# EZS.net
KiCad netlist of a schematic drawn in EAGLE
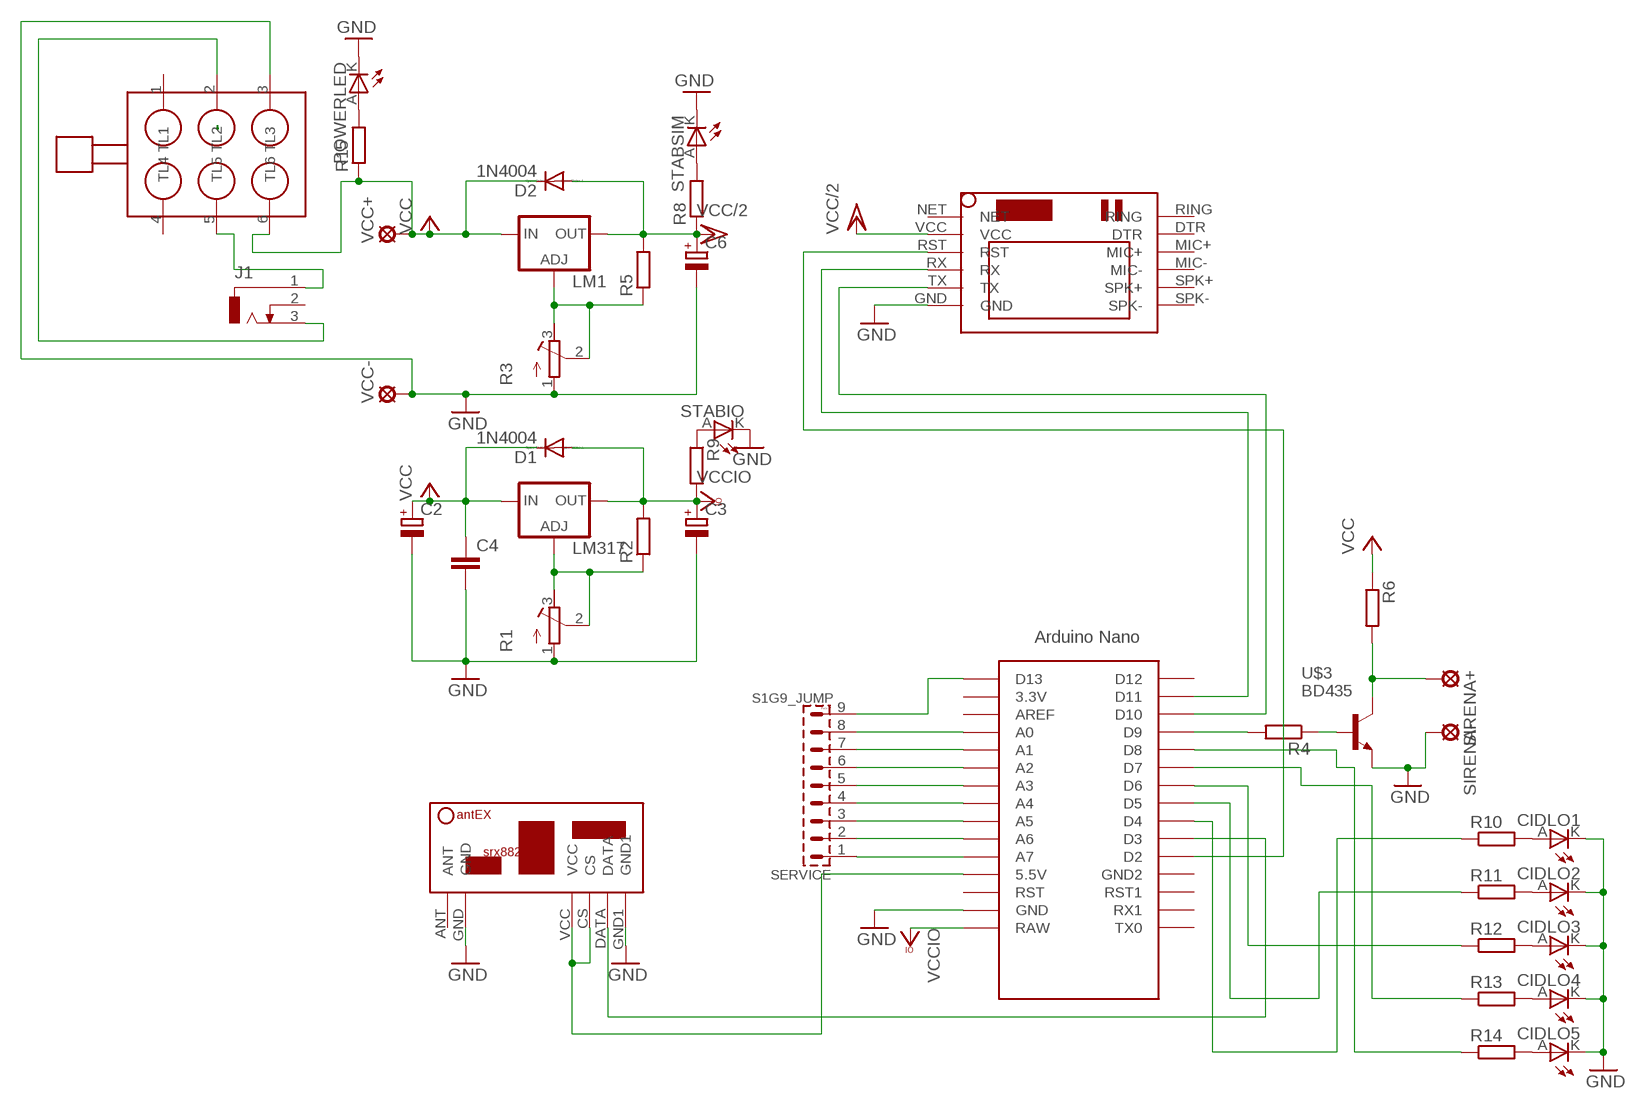
[diagram p0: schematic, sheet 1]

(export (version "E")
  (design (tool "Eeschema 10.0.6"))
  (components
    (comp (ref "C2")
      (value "CPOL-EUE3.5-8")
      (footprint "eagle-import:E3,5-8")
      (libsource (lib "eagle-import") (part "CPOL-EUE3.5-8"))
    )
    (comp (ref "C3")
      (value "CPOL-EUE3.5-8")
      (footprint "eagle-import:E3,5-8")
      (libsource (lib "eagle-import") (part "CPOL-EUE3.5-8"))
    )
    (comp (ref "C4")
      (value "C-EU102-064X133")
      (footprint "eagle-import:C102-064X133")
      (libsource (lib "eagle-import") (part "C-EU102-064X133"))
    )
    (comp (ref "C6")
      (value "CPOL-EUE3.5-8")
      (footprint "eagle-import:E3,5-8")
      (libsource (lib "eagle-import") (part "CPOL-EUE3.5-8"))
    )
    (comp (ref "CIDLO1")
      (value "LEDLED3MM")
      (footprint "eagle-import:LED3MM")
      (libsource (lib "eagle-import") (part "LEDLED3MM"))
    )
    (comp (ref "CIDLO2")
      (value "LEDLED3MM")
      (footprint "eagle-import:LED3MM")
      (libsource (lib "eagle-import") (part "LEDLED3MM"))
    )
    (comp (ref "CIDLO3")
      (value "LEDLED3MM")
      (footprint "eagle-import:LED3MM")
      (libsource (lib "eagle-import") (part "LEDLED3MM"))
    )
    (comp (ref "CIDLO4")
      (value "LEDLED3MM")
      (footprint "eagle-import:LED3MM")
      (libsource (lib "eagle-import") (part "LEDLED3MM"))
    )
    (comp (ref "CIDLO5")
      (value "LEDLED3MM")
      (footprint "eagle-import:LED3MM")
      (libsource (lib "eagle-import") (part "LEDLED3MM"))
    )
    (comp (ref "D1")
      (value "1N4004")
      (footprint "eagle-import:DO41-10")
      (libsource (lib "eagle-import") (part "1N4004"))
    )
    (comp (ref "D2")
      (value "1N4004")
      (footprint "eagle-import:DO41-10")
      (libsource (lib "eagle-import") (part "1N4004"))
    )
    (comp (ref "J1")
      (value "DCJ0303")
      (footprint "eagle-import:DCJ0303")
      (libsource (lib "eagle-import") (part "DCJ0303"))
    )
    (comp (ref "LM1")
      (value "LM317TS")
      (footprint "eagle-import:317TS")
      (libsource (lib "eagle-import") (part "LM317TS"))
    )
    (comp (ref "LM317")
      (value "LM317TS")
      (footprint "eagle-import:317TS")
      (libsource (lib "eagle-import") (part "LM317TS"))
    )
    (comp (ref "POWERLED")
      (value "LEDLED3MM")
      (footprint "eagle-import:LED3MM")
      (libsource (lib "eagle-import") (part "LEDLED3MM"))
    )
    (comp (ref "R1")
      (value "R-TRIMM64Y")
      (footprint "eagle-import:RTRIM64Y")
      (libsource (lib "eagle-import") (part "R-TRIMM64Y"))
    )
    (comp (ref "R2")
      (value "R-EU_0207/10")
      (footprint "eagle-import:0207_10")
      (libsource (lib "eagle-import") (part "R-EU_0207/10"))
    )
    (comp (ref "R3")
      (value "R-TRIMM64Y")
      (footprint "eagle-import:RTRIM64Y")
      (libsource (lib "eagle-import") (part "R-TRIMM64Y"))
    )
    (comp (ref "R4")
      (value "R-EU_0207/10")
      (footprint "eagle-import:0207_10")
      (libsource (lib "eagle-import") (part "R-EU_0207/10"))
    )
    (comp (ref "R5")
      (value "R-EU_0207/10")
      (footprint "eagle-import:0207_10")
      (libsource (lib "eagle-import") (part "R-EU_0207/10"))
    )
    (comp (ref "R6")
      (value "R-EU_0207/10")
      (footprint "eagle-import:0207_10")
      (libsource (lib "eagle-import") (part "R-EU_0207/10"))
    )
    (comp (ref "R8")
      (value "R-EU_0207/10")
      (footprint "eagle-import:0207_10")
      (libsource (lib "eagle-import") (part "R-EU_0207/10"))
    )
    (comp (ref "R9")
      (value "R-EU_0207/10")
      (footprint "eagle-import:0207_10")
      (libsource (lib "eagle-import") (part "R-EU_0207/10"))
    )
    (comp (ref "R10")
      (value "R-EU_0207/10")
      (footprint "eagle-import:0207_10")
      (libsource (lib "eagle-import") (part "R-EU_0207/10"))
    )
    (comp (ref "R11")
      (value "R-EU_0207/10")
      (footprint "eagle-import:0207_10")
      (libsource (lib "eagle-import") (part "R-EU_0207/10"))
    )
    (comp (ref "R12")
      (value "R-EU_0207/10")
      (footprint "eagle-import:0207_10")
      (libsource (lib "eagle-import") (part "R-EU_0207/10"))
    )
    (comp (ref "R13")
      (value "R-EU_0207/10")
      (footprint "eagle-import:0207_10")
      (libsource (lib "eagle-import") (part "R-EU_0207/10"))
    )
    (comp (ref "R14")
      (value "R-EU_0207/10")
      (footprint "eagle-import:0207_10")
      (libsource (lib "eagle-import") (part "R-EU_0207/10"))
    )
    (comp (ref "R15")
      (value "R-EU_0207/10")
      (footprint "eagle-import:0207_10")
      (libsource (lib "eagle-import") (part "R-EU_0207/10"))
    )
    (comp (ref "SERVICE")
      (value "S1G9_JUMP")
      (footprint "eagle-import:S1G9_JUM")
      (libsource (lib "eagle-import") (part "S1G9_JUMP"))
    )
    (comp (ref "SIM800L")
      (value "SIM800LMODULE")
      (footprint "eagle-import:SIM800LMODULE")
      (libsource (lib "eagle-import") (part "SIM800LMODULE"))
    )
    (comp (ref "SIRENA+")
      (value "LSP11")
      (footprint "eagle-import:LSP11")
      (libsource (lib "eagle-import") (part "LSP11"))
    )
    (comp (ref "SIRENA-")
      (value "LSP11")
      (footprint "eagle-import:LSP11")
      (libsource (lib "eagle-import") (part "LSP11"))
    )
    (comp (ref "STABIO")
      (value "LEDLED3MM")
      (footprint "eagle-import:LED3MM")
      (libsource (lib "eagle-import") (part "LEDLED3MM"))
    )
    (comp (ref "STABSIM")
      (value "LEDLED3MM")
      (footprint "eagle-import:LED3MM")
      (libsource (lib "eagle-import") (part "LEDLED3MM"))
    )
    (comp (ref "U$1")
      (value "NANO")
      (footprint "eagle-import:NANO")
      (libsource (lib "eagle-import") (part "NANO"))
    )
    (comp (ref "U$2")
      (value "RSX882")
      (footprint "eagle-import:SRX882")
      (libsource (lib "eagle-import") (part "RSX882"))
    )
    (comp (ref "U$3")
      (value "BD435")
      (footprint "eagle-import:BD435")
      (libsource (lib "eagle-import") (part "BD435"))
    )
    (comp (ref "U$4")
      (value "TLACITKO")
      (footprint "eagle-import:TLACITKO")
      (libsource (lib "eagle-import") (part "TLACITKO"))
    )
    (comp (ref "VCC+")
      (value "LSP11")
      (footprint "eagle-import:LSP11")
      (libsource (lib "eagle-import") (part "LSP11"))
    )
    (comp (ref "VCC-")
      (value "LSP11")
      (footprint "eagle-import:LSP11")
      (libsource (lib "eagle-import") (part "LSP11"))
    )
  )
  (nets
    (net (code "1") (name "GND") (class "Default")
      (node (ref "C2") (pin "-") (pinfunction "-_-") (pintype "passive"))
      (node (ref "C3") (pin "-") (pinfunction "-_-") (pintype "passive"))
      (node (ref "C4") (pin "2") (pinfunction "2_2") (pintype "passive"))
      (node (ref "C6") (pin "-") (pinfunction "-_-") (pintype "passive"))
      (node (ref "CIDLO1") (pin "K") (pinfunction "C_K") (pintype "passive"))
      (node (ref "CIDLO2") (pin "K") (pinfunction "C_K") (pintype "passive"))
      (node (ref "CIDLO3") (pin "K") (pinfunction "C_K") (pintype "passive"))
      (node (ref "CIDLO4") (pin "K") (pinfunction "C_K") (pintype "passive"))
      (node (ref "CIDLO5") (pin "K") (pinfunction "C_K") (pintype "passive"))
      (node (ref "POWERLED") (pin "K") (pinfunction "C_K") (pintype "passive"))
      (node (ref "R1") (pin "1") (pinfunction "A_1") (pintype "passive"))
      (node (ref "R3") (pin "1") (pinfunction "A_1") (pintype "passive"))
      (node (ref "SIM800L") (pin "GND") (pinfunction "GND_GND") (pintype "bidirectional"))
      (node (ref "SIRENA-") (pin "MP") (pinfunction "MP_MP") (pintype "passive"))
      (node (ref "STABIO") (pin "K") (pinfunction "C_K") (pintype "passive"))
      (node (ref "STABSIM") (pin "K") (pinfunction "C_K") (pintype "passive"))
      (node (ref "U$1") (pin "GND") (pinfunction "GND_GND") (pintype "bidirectional"))
      (node (ref "U$2") (pin "GND") (pinfunction "GND_GND") (pintype "bidirectional"))
      (node (ref "U$2") (pin "GND1") (pinfunction "GND1_GND1") (pintype "bidirectional"))
      (node (ref "U$3") (pin "E") (pinfunction "E_E") (pintype "passive"))
      (node (ref "U$4") (pin "3") (pinfunction "TL3_3") (pintype "bidirectional"))
      (node (ref "VCC-") (pin "MP") (pinfunction "MP_MP") (pintype "passive"))
    )
    (net (code "2") (name "Net-(CIDLO1-PadA)") (class "Default")
      (node (ref "CIDLO1") (pin "A") (pinfunction "A_A") (pintype "passive"))
      (node (ref "R10") (pin "2") (pinfunction "2_2") (pintype "passive"))
    )
    (net (code "3") (name "Net-(CIDLO2-PadA)") (class "Default")
      (node (ref "CIDLO2") (pin "A") (pinfunction "A_A") (pintype "passive"))
      (node (ref "R11") (pin "2") (pinfunction "2_2") (pintype "passive"))
    )
    (net (code "4") (name "Net-(CIDLO3-PadA)") (class "Default")
      (node (ref "CIDLO3") (pin "A") (pinfunction "A_A") (pintype "passive"))
      (node (ref "R12") (pin "2") (pinfunction "2_2") (pintype "passive"))
    )
    (net (code "5") (name "Net-(CIDLO4-PadA)") (class "Default")
      (node (ref "CIDLO4") (pin "A") (pinfunction "A_A") (pintype "passive"))
      (node (ref "R13") (pin "2") (pinfunction "2_2") (pintype "passive"))
    )
    (net (code "6") (name "Net-(CIDLO5-PadA)") (class "Default")
      (node (ref "CIDLO5") (pin "A") (pinfunction "A_A") (pintype "passive"))
      (node (ref "R14") (pin "2") (pinfunction "2_2") (pintype "passive"))
    )
    (net (code "7") (name "Net-(LM1-ADJ)") (class "Default")
      (node (ref "LM1") (pin "1") (pinfunction "ADJ_1") (pintype "input"))
      (node (ref "R3") (pin "2") (pinfunction "S_2") (pintype "passive"))
      (node (ref "R3") (pin "3") (pinfunction "E_3") (pintype "passive"))
      (node (ref "R5") (pin "1") (pinfunction "1_1") (pintype "passive"))
    )
    (net (code "8") (name "Net-(LM317-ADJ)") (class "Default")
      (node (ref "LM317") (pin "1") (pinfunction "ADJ_1") (pintype "input"))
      (node (ref "R1") (pin "2") (pinfunction "S_2") (pintype "passive"))
      (node (ref "R1") (pin "3") (pinfunction "E_3") (pintype "passive"))
      (node (ref "R2") (pin "1") (pinfunction "1_1") (pintype "passive"))
    )
    (net (code "9") (name "Net-(POWERLED-PadA)") (class "Default")
      (node (ref "POWERLED") (pin "A") (pinfunction "A_A") (pintype "passive"))
      (node (ref "R15") (pin "2") (pinfunction "2_2") (pintype "passive"))
    )
    (net (code "10") (name "Net-(R4-Pad1)") (class "Default")
      (node (ref "R4") (pin "1") (pinfunction "1_1") (pintype "passive"))
      (node (ref "U$3") (pin "B") (pinfunction "B_B") (pintype "passive"))
    )
    (net (code "11") (name "Net-(R4-Pad2)") (class "Default")
      (node (ref "R4") (pin "2") (pinfunction "2_2") (pintype "passive"))
      (node (ref "U$1") (pin "D9") (pinfunction "D9_D9") (pintype "bidirectional"))
    )
    (net (code "12") (name "Net-(R6-Pad2)") (class "Default")
      (node (ref "R6") (pin "2") (pinfunction "2_2") (pintype "passive"))
      (node (ref "SIRENA+") (pin "MP") (pinfunction "MP_MP") (pintype "passive"))
      (node (ref "U$3") (pin "C") (pinfunction "C_C") (pintype "passive"))
    )
    (net (code "13") (name "Net-(R8-Pad2)") (class "Default")
      (node (ref "R8") (pin "2") (pinfunction "2_2") (pintype "passive"))
      (node (ref "STABSIM") (pin "A") (pinfunction "A_A") (pintype "passive"))
    )
    (net (code "14") (name "Net-(R9-Pad1)") (class "Default")
      (node (ref "R9") (pin "1") (pinfunction "1_1") (pintype "passive"))
      (node (ref "STABIO") (pin "A") (pinfunction "A_A") (pintype "passive"))
    )
    (net (code "15") (name "Net-(R10-Pad1)") (class "Default")
      (node (ref "R10") (pin "1") (pinfunction "1_1") (pintype "passive"))
      (node (ref "U$1") (pin "D4") (pinfunction "D4_D4") (pintype "bidirectional"))
    )
    (net (code "16") (name "Net-(R11-Pad1)") (class "Default")
      (node (ref "R11") (pin "1") (pinfunction "1_1") (pintype "passive"))
      (node (ref "U$1") (pin "D5") (pinfunction "D5_D5") (pintype "bidirectional"))
    )
    (net (code "17") (name "Net-(R12-Pad1)") (class "Default")
      (node (ref "R12") (pin "1") (pinfunction "1_1") (pintype "passive"))
      (node (ref "U$1") (pin "D6") (pinfunction "D6_D6") (pintype "bidirectional"))
    )
    (net (code "18") (name "Net-(R13-Pad1)") (class "Default")
      (node (ref "R13") (pin "1") (pinfunction "1_1") (pintype "passive"))
      (node (ref "U$1") (pin "D7") (pinfunction "D7_D7") (pintype "bidirectional"))
    )
    (net (code "19") (name "Net-(R14-Pad1)") (class "Default")
      (node (ref "R14") (pin "1") (pinfunction "1_1") (pintype "passive"))
      (node (ref "U$1") (pin "D8") (pinfunction "D8_D8") (pintype "bidirectional"))
    )
    (net (code "20") (name "Net-(SERVICE-Pad1)") (class "Default")
      (node (ref "SERVICE") (pin "1") (pinfunction "1_1") (pintype "passive"))
      (node (ref "U$1") (pin "A7") (pinfunction "A7_A7") (pintype "bidirectional"))
    )
    (net (code "21") (name "Net-(SERVICE-Pad2)") (class "Default")
      (node (ref "SERVICE") (pin "2") (pinfunction "2_2") (pintype "passive"))
      (node (ref "U$1") (pin "A6") (pinfunction "A6_A6") (pintype "bidirectional"))
    )
    (net (code "22") (name "Net-(SERVICE-Pad3)") (class "Default")
      (node (ref "SERVICE") (pin "3") (pinfunction "3_3") (pintype "passive"))
      (node (ref "U$1") (pin "A5") (pinfunction "A5_A5") (pintype "bidirectional"))
    )
    (net (code "23") (name "Net-(SERVICE-Pad4)") (class "Default")
      (node (ref "SERVICE") (pin "4") (pinfunction "4_4") (pintype "passive"))
      (node (ref "U$1") (pin "A4") (pinfunction "A4_A4") (pintype "bidirectional"))
    )
    (net (code "24") (name "Net-(SERVICE-Pad5)") (class "Default")
      (node (ref "SERVICE") (pin "5") (pinfunction "5_5") (pintype "passive"))
      (node (ref "U$1") (pin "A3") (pinfunction "A3_A3") (pintype "bidirectional"))
    )
    (net (code "25") (name "Net-(SERVICE-Pad6)") (class "Default")
      (node (ref "SERVICE") (pin "6") (pinfunction "6_6") (pintype "passive"))
      (node (ref "U$1") (pin "A2") (pinfunction "A2_A2") (pintype "bidirectional"))
    )
    (net (code "26") (name "Net-(SERVICE-Pad7)") (class "Default")
      (node (ref "SERVICE") (pin "7") (pinfunction "7_7") (pintype "passive"))
      (node (ref "U$1") (pin "A1") (pinfunction "A1_A1") (pintype "bidirectional"))
    )
    (net (code "27") (name "Net-(SERVICE-Pad8)") (class "Default")
      (node (ref "SERVICE") (pin "8") (pinfunction "8_8") (pintype "passive"))
      (node (ref "U$1") (pin "A0") (pinfunction "A0_A0") (pintype "bidirectional"))
    )
    (net (code "28") (name "Net-(SERVICE-Pad9)") (class "Default")
      (node (ref "SERVICE") (pin "9") (pinfunction "9_9") (pintype "passive"))
      (node (ref "U$1") (pin "D13") (pinfunction "D13_D13") (pintype "bidirectional"))
    )
    (net (code "29") (name "Net-(SIM800L-PadRST)") (class "Default")
      (node (ref "SIM800L") (pin "RST") (pinfunction "RST_RST") (pintype "bidirectional"))
      (node (ref "U$1") (pin "D2") (pinfunction "D2_D2") (pintype "bidirectional"))
    )
    (net (code "30") (name "Net-(SIM800L-PadRX)") (class "Default")
      (node (ref "SIM800L") (pin "RX") (pinfunction "RX_RX") (pintype "bidirectional"))
      (node (ref "U$1") (pin "D11") (pinfunction "D11_D11") (pintype "bidirectional"))
    )
    (net (code "31") (name "Net-(SIM800L-PadTX)") (class "Default")
      (node (ref "SIM800L") (pin "TX") (pinfunction "TX_TX") (pintype "bidirectional"))
      (node (ref "U$1") (pin "D10") (pinfunction "D10_D10") (pintype "bidirectional"))
    )
    (net (code "32") (name "Net-(U$1-5.5V)") (class "Default")
      (node (ref "U$1") (pin "5V") (pinfunction "5.5V_5V") (pintype "bidirectional"))
      (node (ref "U$2") (pin "CS") (pinfunction "CS_CS") (pintype "bidirectional"))
      (node (ref "U$2") (pin "VCC") (pinfunction "VCC_VCC") (pintype "bidirectional"))
    )
    (net (code "33") (name "Net-(U$1-PadD3)") (class "Default")
      (node (ref "U$1") (pin "D3") (pinfunction "D3_D3") (pintype "bidirectional"))
      (node (ref "U$2") (pin "DATA") (pinfunction "DATA_DATA") (pintype "bidirectional"))
    )
    (net (code "34") (name "Net-(U$4-TL2)") (class "Default")
      (node (ref "J1") (pin "3") (pinfunction "3_3") (pintype "passive"))
      (node (ref "U$4") (pin "2") (pinfunction "TL2_2") (pintype "bidirectional"))
    )
    (net (code "35") (name "Net-(U$4-TL5)") (class "Default")
      (node (ref "J1") (pin "1") (pinfunction "1_1") (pintype "passive"))
      (node (ref "U$4") (pin "5") (pinfunction "TL5_5") (pintype "bidirectional"))
    )
    (net (code "36") (name "VCC") (class "Default")
      (node (ref "C2") (pin "+") (pinfunction "+_+") (pintype "passive"))
      (node (ref "C4") (pin "1") (pinfunction "1_1") (pintype "passive"))
      (node (ref "D1") (pin "C") (pinfunction "C_C") (pintype "passive"))
      (node (ref "D2") (pin "C") (pinfunction "C_C") (pintype "passive"))
      (node (ref "LM1") (pin "3") (pinfunction "IN_3") (pintype "input"))
      (node (ref "LM317") (pin "3") (pinfunction "IN_3") (pintype "input"))
      (node (ref "R15") (pin "1") (pinfunction "1_1") (pintype "passive"))
      (node (ref "R6") (pin "1") (pinfunction "1_1") (pintype "passive"))
      (node (ref "U$4") (pin "6") (pinfunction "TL6_6") (pintype "bidirectional"))
      (node (ref "VCC+") (pin "MP") (pinfunction "MP_MP") (pintype "passive"))
    )
    (net (code "37") (name "VCCIO") (class "Default")
      (node (ref "C3") (pin "+") (pinfunction "+_+") (pintype "passive"))
      (node (ref "D1") (pin "A") (pinfunction "A_A") (pintype "passive"))
      (node (ref "LM317") (pin "2") (pinfunction "OUT_2") (pintype "passive"))
      (node (ref "R2") (pin "2") (pinfunction "2_2") (pintype "passive"))
      (node (ref "R9") (pin "2") (pinfunction "2_2") (pintype "passive"))
      (node (ref "U$1") (pin "RAW") (pinfunction "RAW_RAW") (pintype "bidirectional"))
    )
    (net (code "38") (name "VCC{slash}2") (class "Default")
      (node (ref "C6") (pin "+") (pinfunction "+_+") (pintype "passive"))
      (node (ref "D2") (pin "A") (pinfunction "A_A") (pintype "passive"))
      (node (ref "LM1") (pin "2") (pinfunction "OUT_2") (pintype "passive"))
      (node (ref "R5") (pin "2") (pinfunction "2_2") (pintype "passive"))
      (node (ref "R8") (pin "1") (pinfunction "1_1") (pintype "passive"))
      (node (ref "SIM800L") (pin "VCC") (pinfunction "VCC_VCC") (pintype "bidirectional"))
    )
    (net (code "39") (name "unconnected-(J1-Pad2)") (class "Default")
      (node (ref "J1") (pin "2") (pinfunction "2_2") (pintype "passive"))
    )
    (net (code "40") (name "unconnected-(SIM800L-PadDTR)") (class "Default")
      (node (ref "SIM800L") (pin "DTR") (pinfunction "DTR_DTR") (pintype "bidirectional"))
    )
    (net (code "41") (name "unconnected-(SIM800L-PadMIC+)") (class "Default")
      (node (ref "SIM800L") (pin "MIC+") (pinfunction "MIC+_MIC+") (pintype "bidirectional"))
    )
    (net (code "42") (name "unconnected-(SIM800L-PadMIC-)") (class "Default")
      (node (ref "SIM800L") (pin "MIC-") (pinfunction "MIC-_MIC-") (pintype "bidirectional"))
    )
    (net (code "43") (name "unconnected-(SIM800L-PadNET)") (class "Default")
      (node (ref "SIM800L") (pin "NET") (pinfunction "NET_NET") (pintype "bidirectional"))
    )
    (net (code "44") (name "unconnected-(SIM800L-PadRING)") (class "Default")
      (node (ref "SIM800L") (pin "RING") (pinfunction "RING_RING") (pintype "bidirectional"))
    )
    (net (code "45") (name "unconnected-(SIM800L-PadSPK+)") (class "Default")
      (node (ref "SIM800L") (pin "SPK+") (pinfunction "SPK+_SPK+") (pintype "bidirectional"))
    )
    (net (code "46") (name "unconnected-(SIM800L-PadSPK-)") (class "Default")
      (node (ref "SIM800L") (pin "SPK-") (pinfunction "SPK-_SPK-") (pintype "bidirectional"))
    )
    (net (code "47") (name "unconnected-(U$1-GND2-PadGND1)") (class "Default")
      (node (ref "U$1") (pin "GND1") (pinfunction "GND2_GND1") (pintype "bidirectional"))
    )
    (net (code "48") (name "unconnected-(U$1-Pad3.3V)") (class "Default")
      (node (ref "U$1") (pin "3.3V") (pinfunction "3.3V_3.3V") (pintype "bidirectional"))
    )
    (net (code "49") (name "unconnected-(U$1-PadAREF)") (class "Default")
      (node (ref "U$1") (pin "AREF") (pinfunction "AREF_AREF") (pintype "bidirectional"))
    )
    (net (code "50") (name "unconnected-(U$1-PadD12)") (class "Default")
      (node (ref "U$1") (pin "D12") (pinfunction "D12_D12") (pintype "bidirectional"))
    )
    (net (code "51") (name "unconnected-(U$1-PadICSP1)") (class "Default")
      (node (ref "U$1") (pin "ICSP1") (pinfunction "ICSP1_ICSP1") (pintype "bidirectional"))
    )
    (net (code "52") (name "unconnected-(U$1-PadICSP2)") (class "Default")
      (node (ref "U$1") (pin "ICSP2") (pinfunction "ICSP2_ICSP2") (pintype "bidirectional"))
    )
    (net (code "53") (name "unconnected-(U$1-PadICSP3)") (class "Default")
      (node (ref "U$1") (pin "ICSP3") (pinfunction "ICSP3_ICSP3") (pintype "bidirectional"))
    )
    (net (code "54") (name "unconnected-(U$1-PadICSP4)") (class "Default")
      (node (ref "U$1") (pin "ICSP4") (pinfunction "ICSP4_ICSP4") (pintype "bidirectional"))
    )
    (net (code "55") (name "unconnected-(U$1-PadICSP5)") (class "Default")
      (node (ref "U$1") (pin "ICSP5") (pinfunction "ICSP5_ICSP5") (pintype "bidirectional"))
    )
    (net (code "56") (name "unconnected-(U$1-PadICSP6)") (class "Default")
      (node (ref "U$1") (pin "ICSP6") (pinfunction "ICSP6_ICSP6") (pintype "bidirectional"))
    )
    (net (code "57") (name "unconnected-(U$1-PadRST)") (class "Default")
      (node (ref "U$1") (pin "RST") (pinfunction "RST_RST") (pintype "bidirectional"))
    )
    (net (code "58") (name "unconnected-(U$1-PadRST1)") (class "Default")
      (node (ref "U$1") (pin "RST1") (pinfunction "RST1_RST1") (pintype "bidirectional"))
    )
    (net (code "59") (name "unconnected-(U$1-PadRX1)") (class "Default")
      (node (ref "U$1") (pin "RX1") (pinfunction "RX1_RX1") (pintype "bidirectional"))
    )
    (net (code "60") (name "unconnected-(U$1-PadTX0)") (class "Default")
      (node (ref "U$1") (pin "TX0") (pinfunction "TX0_TX0") (pintype "bidirectional"))
    )
    (net (code "61") (name "unconnected-(U$2-PadANT)") (class "Default")
      (node (ref "U$2") (pin "ANT") (pinfunction "ANT_ANT") (pintype "bidirectional"))
    )
    (net (code "62") (name "unconnected-(U$4-TL1-Pad1)") (class "Default")
      (node (ref "U$4") (pin "1") (pinfunction "TL1_1") (pintype "bidirectional"))
    )
    (net (code "63") (name "unconnected-(U$4-TL4-Pad4)") (class "Default")
      (node (ref "U$4") (pin "4") (pinfunction "TL4_4") (pintype "bidirectional"))
    )
  )
)
